# Weigh_scale1.net
KiCad netlist of a schematic drawn in EAGLE
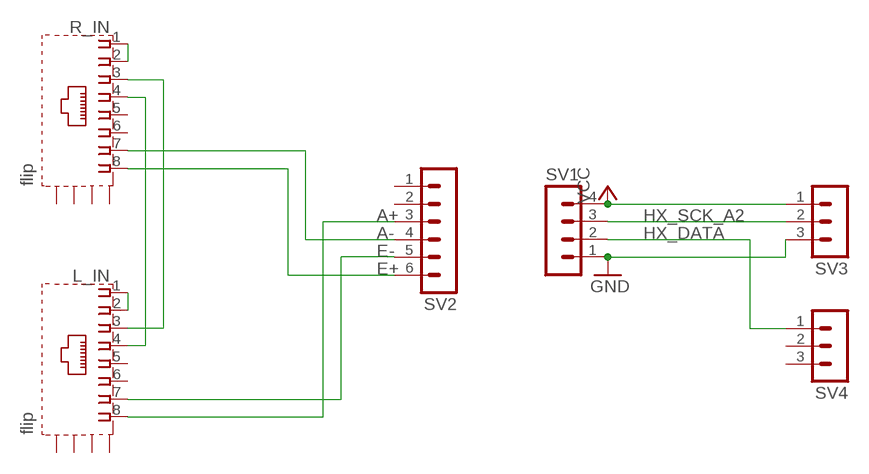
[diagram p0: schematic, sheet 1]

(export (version "E")
  (design (tool "Eeschema 10.0.6"))
  (components
    (comp (ref "L_IN")
      (value "flip")
      (footprint "eagle-import:RJ45-SHIELD2")
      (fields (field (name "MPN") "RJ45-6L2-B"))
      (libsource (lib "eagle-import") (part "RJ452-B-6L"))
    )
    (comp (ref "R_IN")
      (value "flip")
      (footprint "eagle-import:RJ45-SHIELD2")
      (fields (field (name "MPN") "RJ45-6L2-B"))
      (libsource (lib "eagle-import") (part "RJ452-B-6L"))
    )
    (comp (ref "SV1")
      (value "MA04-1")
      (footprint "eagle-import:MA04-1")
      (libsource (lib "eagle-import") (part "MA04-1"))
    )
    (comp (ref "SV2")
      (value "MA06-1")
      (footprint "eagle-import:MA06-1")
      (libsource (lib "eagle-import") (part "MA06-1"))
    )
    (comp (ref "SV3")
      (value "MA03-1")
      (footprint "eagle-import:MA03-1")
      (libsource (lib "eagle-import") (part "MA03-1"))
    )
    (comp (ref "SV4")
      (value "MA03-1")
      (footprint "eagle-import:MA03-1")
      (libsource (lib "eagle-import") (part "MA03-1"))
    )
  )
  (nets
    (net (code "1") (name "/A+") (class "Default")
      (node (ref "L_IN") (pin "8") (pinfunction "8_8") (pintype "passive"))
      (node (ref "SV2") (pin "3") (pinfunction "3_3") (pintype "passive"))
    )
    (net (code "2") (name "/A-") (class "Default")
      (node (ref "R_IN") (pin "7") (pinfunction "7_7") (pintype "passive"))
      (node (ref "SV2") (pin "4") (pinfunction "4_4") (pintype "passive"))
    )
    (net (code "3") (name "/E+") (class "Default")
      (node (ref "R_IN") (pin "8") (pinfunction "8_8") (pintype "passive"))
      (node (ref "SV2") (pin "6") (pinfunction "6_6") (pintype "passive"))
    )
    (net (code "4") (name "/E-") (class "Default")
      (node (ref "L_IN") (pin "7") (pinfunction "7_7") (pintype "passive"))
      (node (ref "SV2") (pin "5") (pinfunction "5_5") (pintype "passive"))
    )
    (net (code "5") (name "/HX_DATA") (class "Default")
      (node (ref "SV1") (pin "2") (pinfunction "2_2") (pintype "passive"))
      (node (ref "SV4") (pin "1") (pinfunction "1_1") (pintype "passive"))
    )
    (net (code "6") (name "/HX_SCK_A2") (class "Default")
      (node (ref "SV1") (pin "3") (pinfunction "3_3") (pintype "passive"))
      (node (ref "SV3") (pin "2") (pinfunction "2_2") (pintype "passive"))
    )
    (net (code "7") (name "GND") (class "Default")
      (node (ref "SV1") (pin "1") (pinfunction "1_1") (pintype "passive"))
      (node (ref "SV3") (pin "3") (pinfunction "3_3") (pintype "passive"))
    )
    (net (code "8") (name "Net-(L_IN-Pad1)") (class "Default")
      (node (ref "L_IN") (pin "1") (pinfunction "1_1") (pintype "passive"))
      (node (ref "L_IN") (pin "2") (pinfunction "2_2") (pintype "passive"))
    )
    (net (code "9") (name "Net-(L_IN-Pad3)") (class "Default")
      (node (ref "L_IN") (pin "3") (pinfunction "3_3") (pintype "passive"))
      (node (ref "R_IN") (pin "3") (pinfunction "3_3") (pintype "passive"))
    )
    (net (code "10") (name "Net-(L_IN-Pad4)") (class "Default")
      (node (ref "L_IN") (pin "4") (pinfunction "4_4") (pintype "passive"))
      (node (ref "R_IN") (pin "4") (pinfunction "4_4") (pintype "passive"))
    )
    (net (code "11") (name "Net-(R_IN-Pad1)") (class "Default")
      (node (ref "R_IN") (pin "1") (pinfunction "1_1") (pintype "passive"))
      (node (ref "R_IN") (pin "2") (pinfunction "2_2") (pintype "passive"))
    )
    (net (code "12") (name "VCC") (class "Default")
      (node (ref "SV1") (pin "4") (pinfunction "4_4") (pintype "passive"))
      (node (ref "SV3") (pin "1") (pinfunction "1_1") (pintype "passive"))
    )
    (net (code "13") (name "unconnected-(L_IN-Pad5)") (class "Default")
      (node (ref "L_IN") (pin "5") (pinfunction "5_5") (pintype "passive"))
    )
    (net (code "14") (name "unconnected-(L_IN-Pad6)") (class "Default")
      (node (ref "L_IN") (pin "6") (pinfunction "6_6") (pintype "passive"))
    )
    (net (code "15") (name "unconnected-(L_IN-S-PadS1)") (class "Default")
      (node (ref "L_IN") (pin "S1") (pinfunction "S_S1") (pintype "passive"))
    )
    (net (code "16") (name "unconnected-(L_IN-S-PadS2)") (class "Default")
      (node (ref "L_IN") (pin "S2") (pinfunction "S_S2") (pintype "passive"))
    )
    (net (code "17") (name "unconnected-(L_IN-S-PadS3)") (class "Default")
      (node (ref "L_IN") (pin "S3") (pinfunction "S_S3") (pintype "passive"))
    )
    (net (code "18") (name "unconnected-(L_IN-S-PadS4)") (class "Default")
      (node (ref "L_IN") (pin "S4") (pinfunction "S_S4") (pintype "passive"))
    )
    (net (code "19") (name "unconnected-(R_IN-Pad5)") (class "Default")
      (node (ref "R_IN") (pin "5") (pinfunction "5_5") (pintype "passive"))
    )
    (net (code "20") (name "unconnected-(R_IN-Pad6)") (class "Default")
      (node (ref "R_IN") (pin "6") (pinfunction "6_6") (pintype "passive"))
    )
    (net (code "21") (name "unconnected-(R_IN-S-PadS1)") (class "Default")
      (node (ref "R_IN") (pin "S1") (pinfunction "S_S1") (pintype "passive"))
    )
    (net (code "22") (name "unconnected-(R_IN-S-PadS2)") (class "Default")
      (node (ref "R_IN") (pin "S2") (pinfunction "S_S2") (pintype "passive"))
    )
    (net (code "23") (name "unconnected-(R_IN-S-PadS3)") (class "Default")
      (node (ref "R_IN") (pin "S3") (pinfunction "S_S3") (pintype "passive"))
    )
    (net (code "24") (name "unconnected-(R_IN-S-PadS4)") (class "Default")
      (node (ref "R_IN") (pin "S4") (pinfunction "S_S4") (pintype "passive"))
    )
    (net (code "25") (name "unconnected-(SV2-Pad1)") (class "Default")
      (node (ref "SV2") (pin "1") (pinfunction "1_1") (pintype "passive"))
    )
    (net (code "26") (name "unconnected-(SV2-Pad2)") (class "Default")
      (node (ref "SV2") (pin "2") (pinfunction "2_2") (pintype "passive"))
    )
    (net (code "27") (name "unconnected-(SV4-Pad2)") (class "Default")
      (node (ref "SV4") (pin "2") (pinfunction "2_2") (pintype "passive"))
    )
    (net (code "28") (name "unconnected-(SV4-Pad3)") (class "Default")
      (node (ref "SV4") (pin "3") (pinfunction "3_3") (pintype "passive"))
    )
  )
)
